# TCAN330_PINOUT.net
KiCad netlist of a schematic drawn in Altium Designer
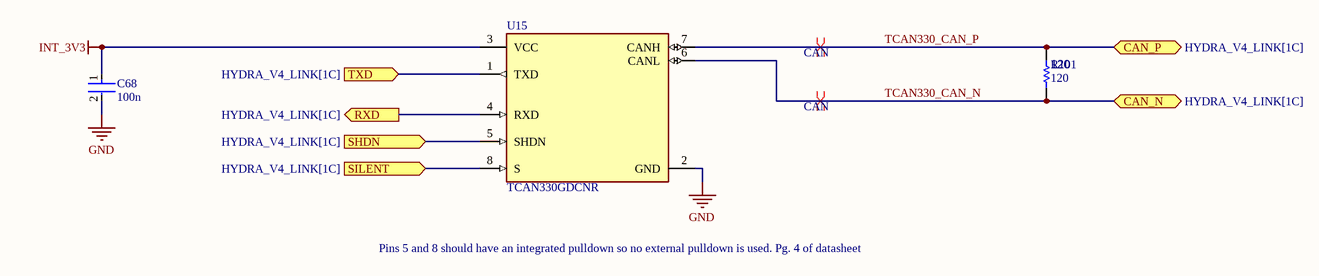
[diagram p0: TCAN330_PINOUT.SchDoc]

(export (version "E")
  (design (tool "Eeschema 10.0.6"))
  (components
    (comp (ref "C68")
      (value "100n")
      (footprint "FP-0402-L_1_0_0_05-W_0_5-IPC_A")
      (description "LARGE PADS, 0402 CAP, CHANGE COMMENT TO MATCH REAL P/N")
      (libsource (lib "Space Concordia") (part "b4654b650e69147ec39a6b967a45e02"))
    )
    (comp (ref "R101")
      (value "120")
      (footprint "R0603B")
      (description "Resistor")
      (fields (field (name "ALTIUM_VALUE") "120"))
      (libsource (lib "Space Concordia") (part "Resistor"))
    )
    (comp (ref "U15")
      (value "TCAN330GDCNR")
      (footprint "FP-DCN0008A-MFG")
      (description "IC TRANSCEIVER 1/1 SOT23-8")
      (libsource (lib "Altium Content Vault") (part "22681b49c22ad38c6a4e12e04c36c7a"))
    )
  )
  (nets
    (net (code "1") (name "/RXD") (class "Default")
      (node (ref "U15") (pin "4") (pinfunction "RXD_4") (pintype "input"))
    )
    (net (code "2") (name "/SHDN") (class "Default")
      (node (ref "U15") (pin "5") (pinfunction "SHDN_5") (pintype "input"))
    )
    (net (code "3") (name "/SILENT") (class "Default")
      (node (ref "U15") (pin "8") (pinfunction "S_8") (pintype "input"))
    )
    (net (code "4") (name "/TCAN330_CAN_N") (class "Default")
      (node (ref "R101") (pin "1") (pinfunction "1_1") (pintype "passive"))
      (node (ref "U15") (pin "6") (pinfunction "CANL_6") (pintype "bidirectional"))
    )
    (net (code "5") (name "/TCAN330_CAN_P") (class "Default")
      (node (ref "R101") (pin "2") (pinfunction "2_2") (pintype "passive"))
      (node (ref "U15") (pin "7") (pinfunction "CANH_7") (pintype "bidirectional"))
    )
    (net (code "6") (name "/TXD") (class "Default")
      (node (ref "U15") (pin "1") (pinfunction "TXD_1") (pintype "output"))
    )
    (net (code "7") (name "GND") (class "Default")
      (node (ref "C68") (pin "2") (pinfunction "2_2") (pintype "passive"))
      (node (ref "U15") (pin "2") (pinfunction "GND_2") (pintype "power_in"))
    )
    (net (code "8") (name "INT_3V3") (class "Default")
      (node (ref "C68") (pin "1") (pinfunction "1_1") (pintype "passive"))
      (node (ref "U15") (pin "3") (pinfunction "VCC_3") (pintype "power_in"))
    )
  )
)
